# CC2530.net
KiCad netlist of a schematic drawn in Altium Designer
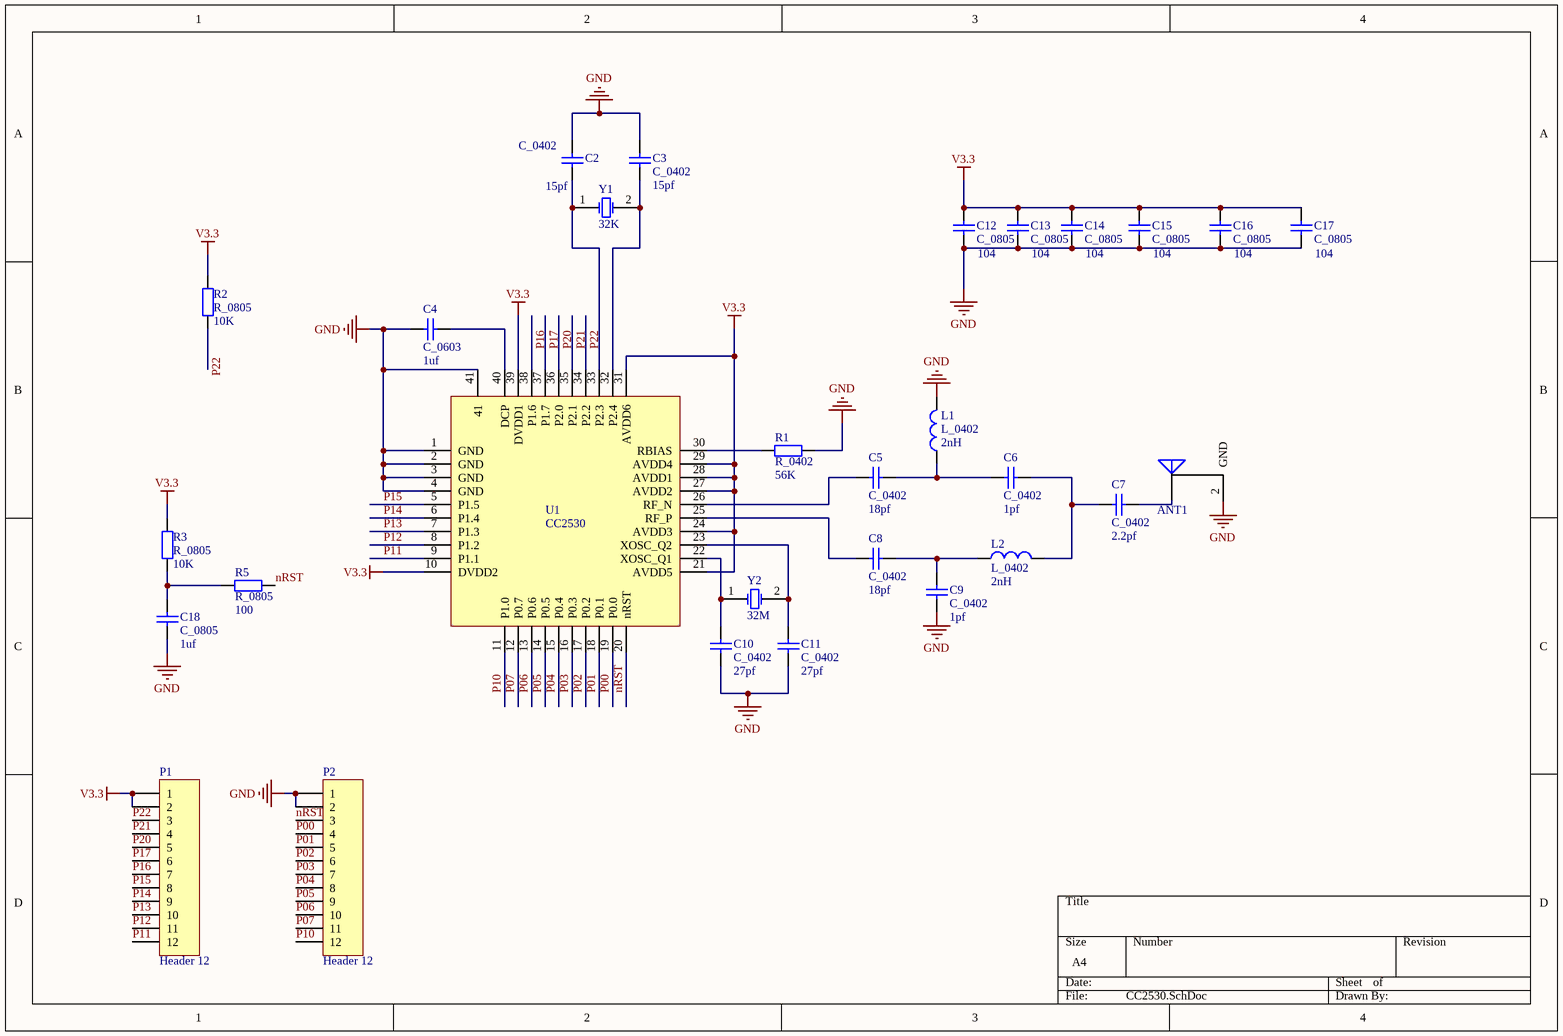
[diagram p0: CC2530.SchDoc]

(export (version "E")
  (design (tool "Eeschema 10.0.6"))
  (components
    (comp (ref "ANT1") (value "ANT") (footprint "ANT") (libsource (lib "My_Int_Lib") (part "ANT")))
    (comp (ref "C2")
      (value "C_0402")
      (footprint "M_0402")
      (fields (field (name "ALTIUM_VALUE") "15pf"))
      (libsource (lib "My_Int_Lib") (part "C_0805"))
    )
    (comp (ref "C3")
      (value "C_0402")
      (footprint "M_0402")
      (fields (field (name "ALTIUM_VALUE") "15pf"))
      (libsource (lib "My_Int_Lib") (part "C_0805"))
    )
    (comp (ref "C4")
      (value "C_0603")
      (footprint "M_0402")
      (fields (field (name "ALTIUM_VALUE") "1uf"))
      (libsource (lib "My_Int_Lib") (part "C_0805"))
    )
    (comp (ref "C5")
      (value "C_0402")
      (footprint "M_0402")
      (fields (field (name "ALTIUM_VALUE") "18pf"))
      (libsource (lib "My_Int_Lib") (part "C_0402"))
    )
    (comp (ref "C6")
      (value "C_0402")
      (footprint "M_0402")
      (fields (field (name "ALTIUM_VALUE") "1pf"))
      (libsource (lib "My_Int_Lib") (part "C_0402"))
    )
    (comp (ref "C7")
      (value "C_0402")
      (footprint "M_0402")
      (fields (field (name "ALTIUM_VALUE") "2.2pf"))
      (libsource (lib "My_Int_Lib") (part "C_0402"))
    )
    (comp (ref "C8")
      (value "C_0402")
      (footprint "M_0402")
      (fields (field (name "ALTIUM_VALUE") "18pf"))
      (libsource (lib "My_Int_Lib") (part "C_0402"))
    )
    (comp (ref "C9")
      (value "C_0402")
      (footprint "M_0402")
      (fields (field (name "ALTIUM_VALUE") "1pf"))
      (libsource (lib "My_Int_Lib") (part "C_0402"))
    )
    (comp (ref "C10")
      (value "C_0402")
      (footprint "M_0402")
      (fields (field (name "ALTIUM_VALUE") "27pf"))
      (libsource (lib "My_Int_Lib") (part "C_0805"))
    )
    (comp (ref "C11")
      (value "C_0402")
      (footprint "M_0402")
      (fields (field (name "ALTIUM_VALUE") "27pf"))
      (libsource (lib "My_Int_Lib") (part "C_0805"))
    )
    (comp (ref "C12")
      (value "C_0805")
      (footprint "M_0402")
      (fields (field (name "ALTIUM_VALUE") "104"))
      (libsource (lib "My_Int_Lib") (part "C_0805"))
    )
    (comp (ref "C13")
      (value "C_0805")
      (footprint "M_0402")
      (fields (field (name "ALTIUM_VALUE") "104"))
      (libsource (lib "My_Int_Lib") (part "C_0805"))
    )
    (comp (ref "C14")
      (value "C_0805")
      (footprint "M_0402")
      (fields (field (name "ALTIUM_VALUE") "104"))
      (libsource (lib "My_Int_Lib") (part "C_0805"))
    )
    (comp (ref "C15")
      (value "C_0805")
      (footprint "M_0402")
      (fields (field (name "ALTIUM_VALUE") "104"))
      (libsource (lib "My_Int_Lib") (part "C_0805"))
    )
    (comp (ref "C16")
      (value "C_0805")
      (footprint "M_0402")
      (fields (field (name "ALTIUM_VALUE") "104"))
      (libsource (lib "My_Int_Lib") (part "C_0805"))
    )
    (comp (ref "C17")
      (value "C_0805")
      (footprint "M_0402")
      (fields (field (name "ALTIUM_VALUE") "104"))
      (libsource (lib "My_Int_Lib") (part "C_0805"))
    )
    (comp (ref "C18")
      (value "C_0805")
      (footprint "M_0402")
      (fields (field (name "ALTIUM_VALUE") "1uf"))
      (libsource (lib "My_Int_Lib") (part "C_0805"))
    )
    (comp (ref "L1")
      (value "L_0402")
      (footprint "M_0402")
      (fields (field (name "ALTIUM_VALUE") "2nH"))
      (libsource (lib "My_Int_Lib") (part "L_0402"))
    )
    (comp (ref "L2")
      (value "L_0402")
      (footprint "M_0402")
      (fields (field (name "ALTIUM_VALUE") "2nH"))
      (libsource (lib "My_Int_Lib") (part "L_0402"))
    )
    (comp (ref "P1")
      (value "Header 12")
      (footprint "Header-2.0")
      (description "Header, 12-Pin")
      (fields (field (name "PUBLISHER") "Altium Limited"))
      (libsource (lib "Miscellaneous Connectors") (part "Header 12"))
    )
    (comp (ref "P2")
      (value "Header 12")
      (footprint "Header-2.0")
      (description "Header, 12-Pin")
      (fields (field (name "PUBLISHER") "Altium Limited"))
      (libsource (lib "Miscellaneous Connectors") (part "Header 12"))
    )
    (comp (ref "R1")
      (value "R_0402")
      (footprint "M_0402")
      (fields (field (name "ALTIUM_VALUE") "56K"))
      (libsource (lib "My_Int_Lib") (part "R_0805"))
    )
    (comp (ref "R2")
      (value "R_0805")
      (footprint "M_0402")
      (fields (field (name "ALTIUM_VALUE") "10K"))
      (libsource (lib "") (part "R_0805_1"))
    )
    (comp (ref "R3")
      (value "R_0805")
      (footprint "M_0402")
      (fields (field (name "ALTIUM_VALUE") "10K"))
      (libsource (lib "") (part "R_0805_1"))
    )
    (comp (ref "R5")
      (value "R_0805")
      (footprint "M_0402")
      (fields (field (name "ALTIUM_VALUE") "100"))
      (libsource (lib "My_Int_Lib") (part "R_0805"))
    )
    (comp (ref "U1") (value "CC2530") (footprint "QFN40") (libsource (lib "My_Int_Lib") (part "CC2530")))
    (comp (ref "Y1") (value "32K") (footprint "XTAL_32K_2P") (libsource (lib "My_Int_Lib") (part "X_32K_2P")))
    (comp (ref "Y2")
      (value "32M")
      (footprint "XTAL_32M_SMD")
      (libsource (lib "My_Int_Lib") (part "X_32M_SMD"))
    )
  )
  (nets
    (net (code "1") (name "/P00") (class "Default")
      (node (ref "P2") (pin "4") (pinfunction "4_4") (pintype "passive"))
      (node (ref "U1") (pin "19") (pinfunction "P0.0_19") (pintype "passive"))
    )
    (net (code "2") (name "/P01") (class "Default")
      (node (ref "P2") (pin "5") (pinfunction "5_5") (pintype "passive"))
      (node (ref "U1") (pin "18") (pinfunction "P0.1_18") (pintype "passive"))
    )
    (net (code "3") (name "/P02") (class "Default")
      (node (ref "P2") (pin "6") (pinfunction "6_6") (pintype "passive"))
      (node (ref "U1") (pin "17") (pinfunction "P0.2_17") (pintype "passive"))
    )
    (net (code "4") (name "/P03") (class "Default")
      (node (ref "P2") (pin "7") (pinfunction "7_7") (pintype "passive"))
      (node (ref "U1") (pin "16") (pinfunction "P0.3_16") (pintype "passive"))
    )
    (net (code "5") (name "/P04") (class "Default")
      (node (ref "P2") (pin "8") (pinfunction "8_8") (pintype "passive"))
      (node (ref "U1") (pin "15") (pinfunction "P0.4_15") (pintype "passive"))
    )
    (net (code "6") (name "/P05") (class "Default")
      (node (ref "P2") (pin "9") (pinfunction "9_9") (pintype "passive"))
      (node (ref "U1") (pin "14") (pinfunction "P0.5_14") (pintype "passive"))
    )
    (net (code "7") (name "/P06") (class "Default")
      (node (ref "P2") (pin "10") (pinfunction "10_10") (pintype "passive"))
      (node (ref "U1") (pin "13") (pinfunction "P0.6_13") (pintype "passive"))
    )
    (net (code "8") (name "/P07") (class "Default")
      (node (ref "P2") (pin "11") (pinfunction "11_11") (pintype "passive"))
      (node (ref "U1") (pin "12") (pinfunction "P0.7_12") (pintype "passive"))
    )
    (net (code "9") (name "/P10") (class "Default")
      (node (ref "P2") (pin "12") (pinfunction "12_12") (pintype "passive"))
      (node (ref "U1") (pin "11") (pinfunction "P1.0_11") (pintype "passive"))
    )
    (net (code "10") (name "/P11") (class "Default")
      (node (ref "P1") (pin "12") (pinfunction "12_12") (pintype "passive"))
      (node (ref "U1") (pin "9") (pinfunction "P1.1_9") (pintype "passive"))
    )
    (net (code "11") (name "/P12") (class "Default")
      (node (ref "P1") (pin "11") (pinfunction "11_11") (pintype "passive"))
      (node (ref "U1") (pin "8") (pinfunction "P1.2_8") (pintype "passive"))
    )
    (net (code "12") (name "/P13") (class "Default")
      (node (ref "P1") (pin "10") (pinfunction "10_10") (pintype "passive"))
      (node (ref "U1") (pin "7") (pinfunction "P1.3_7") (pintype "passive"))
    )
    (net (code "13") (name "/P14") (class "Default")
      (node (ref "P1") (pin "9") (pinfunction "9_9") (pintype "passive"))
      (node (ref "U1") (pin "6") (pinfunction "P1.4_6") (pintype "passive"))
    )
    (net (code "14") (name "/P15") (class "Default")
      (node (ref "P1") (pin "8") (pinfunction "8_8") (pintype "passive"))
      (node (ref "U1") (pin "5") (pinfunction "P1.5_5") (pintype "passive"))
    )
    (net (code "15") (name "/P16") (class "Default")
      (node (ref "P1") (pin "7") (pinfunction "7_7") (pintype "passive"))
      (node (ref "U1") (pin "38") (pinfunction "P1.6_38") (pintype "passive"))
    )
    (net (code "16") (name "/P17") (class "Default")
      (node (ref "P1") (pin "6") (pinfunction "6_6") (pintype "passive"))
      (node (ref "U1") (pin "37") (pinfunction "P1.7_37") (pintype "passive"))
    )
    (net (code "17") (name "/P20") (class "Default")
      (node (ref "P1") (pin "5") (pinfunction "5_5") (pintype "passive"))
      (node (ref "U1") (pin "36") (pinfunction "P2.0_36") (pintype "passive"))
    )
    (net (code "18") (name "/P21") (class "Default")
      (node (ref "P1") (pin "4") (pinfunction "4_4") (pintype "passive"))
      (node (ref "U1") (pin "35") (pinfunction "P2.1_35") (pintype "passive"))
    )
    (net (code "19") (name "/P22") (class "Default")
      (node (ref "P1") (pin "3") (pinfunction "3_3") (pintype "passive"))
      (node (ref "R2") (pin "1") (pinfunction "1_1") (pintype "passive"))
      (node (ref "U1") (pin "34") (pinfunction "P2.2_34") (pintype "passive"))
    )
    (net (code "20") (name "/nRST") (class "Default")
      (node (ref "P2") (pin "3") (pinfunction "3_3") (pintype "passive"))
      (node (ref "R5") (pin "2") (pinfunction "2_2") (pintype "passive"))
      (node (ref "U1") (pin "20") (pinfunction "nRST_20") (pintype "passive"))
    )
    (net (code "21") (name "GND") (class "Default")
      (node (ref "ANT1") (pin "2") (pinfunction "GND_2") (pintype "passive"))
      (node (ref "C10") (pin "1") (pinfunction "1_1") (pintype "passive"))
      (node (ref "C11") (pin "1") (pinfunction "1_1") (pintype "passive"))
      (node (ref "C12") (pin "1") (pinfunction "1_1") (pintype "passive"))
      (node (ref "C13") (pin "1") (pinfunction "1_1") (pintype "passive"))
      (node (ref "C14") (pin "1") (pinfunction "1_1") (pintype "passive"))
      (node (ref "C15") (pin "1") (pinfunction "1_1") (pintype "passive"))
      (node (ref "C16") (pin "1") (pinfunction "1_1") (pintype "passive"))
      (node (ref "C17") (pin "1") (pinfunction "1_1") (pintype "passive"))
      (node (ref "C18") (pin "1") (pinfunction "1_1") (pintype "passive"))
      (node (ref "C2") (pin "2") (pinfunction "2_2") (pintype "passive"))
      (node (ref "C3") (pin "2") (pinfunction "2_2") (pintype "passive"))
      (node (ref "C4") (pin "2") (pinfunction "2_2") (pintype "passive"))
      (node (ref "C9") (pin "1") (pinfunction "1_1") (pintype "passive"))
      (node (ref "L1") (pin "2") (pinfunction "2_2") (pintype "passive"))
      (node (ref "P2") (pin "1") (pinfunction "1_1") (pintype "passive"))
      (node (ref "P2") (pin "2") (pinfunction "2_2") (pintype "passive"))
      (node (ref "R1") (pin "2") (pinfunction "2_2") (pintype "passive"))
      (node (ref "U1") (pin "1") (pinfunction "GND_1") (pintype "passive"))
      (node (ref "U1") (pin "2") (pinfunction "GND_2") (pintype "passive"))
      (node (ref "U1") (pin "3") (pinfunction "GND_3") (pintype "passive"))
      (node (ref "U1") (pin "4") (pinfunction "GND_4") (pintype "passive"))
      (node (ref "U1") (pin "41") (pinfunction "41_41") (pintype "passive"))
    )
    (net (code "22") (name "Net-(ANT1-A)") (class "Default")
      (node (ref "ANT1") (pin "1") (pinfunction "A_1") (pintype "passive"))
      (node (ref "C7") (pin "2") (pinfunction "2_2") (pintype "passive"))
    )
    (net (code "23") (name "Net-(C5-Pad2)") (class "Default")
      (node (ref "C5") (pin "2") (pinfunction "2_2") (pintype "passive"))
      (node (ref "C6") (pin "1") (pinfunction "1_1") (pintype "passive"))
      (node (ref "L1") (pin "1") (pinfunction "1_1") (pintype "passive"))
    )
    (net (code "24") (name "Net-(C6-Pad2)") (class "Default")
      (node (ref "C6") (pin "2") (pinfunction "2_2") (pintype "passive"))
      (node (ref "C7") (pin "1") (pinfunction "1_1") (pintype "passive"))
      (node (ref "L2") (pin "2") (pinfunction "2_2") (pintype "passive"))
    )
    (net (code "25") (name "Net-(C8-Pad2)") (class "Default")
      (node (ref "C8") (pin "2") (pinfunction "2_2") (pintype "passive"))
      (node (ref "C9") (pin "2") (pinfunction "2_2") (pintype "passive"))
      (node (ref "L2") (pin "1") (pinfunction "1_1") (pintype "passive"))
    )
    (net (code "26") (name "Net-(C18-Pad2)") (class "Default")
      (node (ref "C18") (pin "2") (pinfunction "2_2") (pintype "passive"))
      (node (ref "R3") (pin "1") (pinfunction "1_1") (pintype "passive"))
      (node (ref "R5") (pin "1") (pinfunction "1_1") (pintype "passive"))
    )
    (net (code "27") (name "Net-(U1-DCP)") (class "Default")
      (node (ref "C4") (pin "1") (pinfunction "1_1") (pintype "passive"))
      (node (ref "U1") (pin "40") (pinfunction "DCP_40") (pintype "passive"))
    )
    (net (code "28") (name "Net-(U1-P2.3)") (class "Default")
      (node (ref "C2") (pin "1") (pinfunction "1_1") (pintype "passive"))
      (node (ref "U1") (pin "33") (pinfunction "P2.3_33") (pintype "passive"))
      (node (ref "Y1") (pin "1") (pinfunction "OSC1_1") (pintype "passive"))
    )
    (net (code "29") (name "Net-(U1-P2.4)") (class "Default")
      (node (ref "C3") (pin "1") (pinfunction "1_1") (pintype "passive"))
      (node (ref "U1") (pin "32") (pinfunction "P2.4_32") (pintype "passive"))
      (node (ref "Y1") (pin "2") (pinfunction "OSC2_2") (pintype "passive"))
    )
    (net (code "30") (name "Net-(U1-RBIAS)") (class "Default")
      (node (ref "R1") (pin "1") (pinfunction "1_1") (pintype "passive"))
      (node (ref "U1") (pin "30") (pinfunction "RBIAS_30") (pintype "passive"))
    )
    (net (code "31") (name "Net-(U1-RF_N)") (class "Default")
      (node (ref "C5") (pin "1") (pinfunction "1_1") (pintype "passive"))
      (node (ref "U1") (pin "26") (pinfunction "RF_N_26") (pintype "passive"))
    )
    (net (code "32") (name "Net-(U1-RF_P)") (class "Default")
      (node (ref "C8") (pin "1") (pinfunction "1_1") (pintype "passive"))
      (node (ref "U1") (pin "25") (pinfunction "RF_P_25") (pintype "passive"))
    )
    (net (code "33") (name "Net-(U1-XOSC_Q1)") (class "Default")
      (node (ref "C10") (pin "2") (pinfunction "2_2") (pintype "passive"))
      (node (ref "U1") (pin "22") (pinfunction "XOSC_Q1_22") (pintype "passive"))
      (node (ref "Y2") (pin "1") (pinfunction "OSC1_1") (pintype "passive"))
    )
    (net (code "34") (name "Net-(U1-XOSC_Q2)") (class "Default")
      (node (ref "C11") (pin "2") (pinfunction "2_2") (pintype "passive"))
      (node (ref "U1") (pin "23") (pinfunction "XOSC_Q2_23") (pintype "passive"))
      (node (ref "Y2") (pin "2") (pinfunction "OSC2_2") (pintype "passive"))
    )
    (net (code "35") (name "V3.3") (class "Default")
      (node (ref "C12") (pin "2") (pinfunction "2_2") (pintype "passive"))
      (node (ref "C13") (pin "2") (pinfunction "2_2") (pintype "passive"))
      (node (ref "C14") (pin "2") (pinfunction "2_2") (pintype "passive"))
      (node (ref "C15") (pin "2") (pinfunction "2_2") (pintype "passive"))
      (node (ref "C16") (pin "2") (pinfunction "2_2") (pintype "passive"))
      (node (ref "C17") (pin "2") (pinfunction "2_2") (pintype "passive"))
      (node (ref "P1") (pin "1") (pinfunction "1_1") (pintype "passive"))
      (node (ref "P1") (pin "2") (pinfunction "2_2") (pintype "passive"))
      (node (ref "R2") (pin "2") (pinfunction "2_2") (pintype "passive"))
      (node (ref "R3") (pin "2") (pinfunction "2_2") (pintype "passive"))
      (node (ref "U1") (pin "10") (pinfunction "DVDD2_10") (pintype "passive"))
      (node (ref "U1") (pin "21") (pinfunction "AVDD5_21") (pintype "passive"))
      (node (ref "U1") (pin "24") (pinfunction "AVDD3_24") (pintype "passive"))
      (node (ref "U1") (pin "27") (pinfunction "AVDD2_27") (pintype "passive"))
      (node (ref "U1") (pin "28") (pinfunction "AVDD1_28") (pintype "passive"))
      (node (ref "U1") (pin "29") (pinfunction "AVDD4_29") (pintype "passive"))
      (node (ref "U1") (pin "31") (pinfunction "AVDD6_31") (pintype "passive"))
      (node (ref "U1") (pin "39") (pinfunction "DVDD1_39") (pintype "passive"))
    )
  )
)
